# main_board.net
KiCad netlist of a schematic drawn in EAGLE
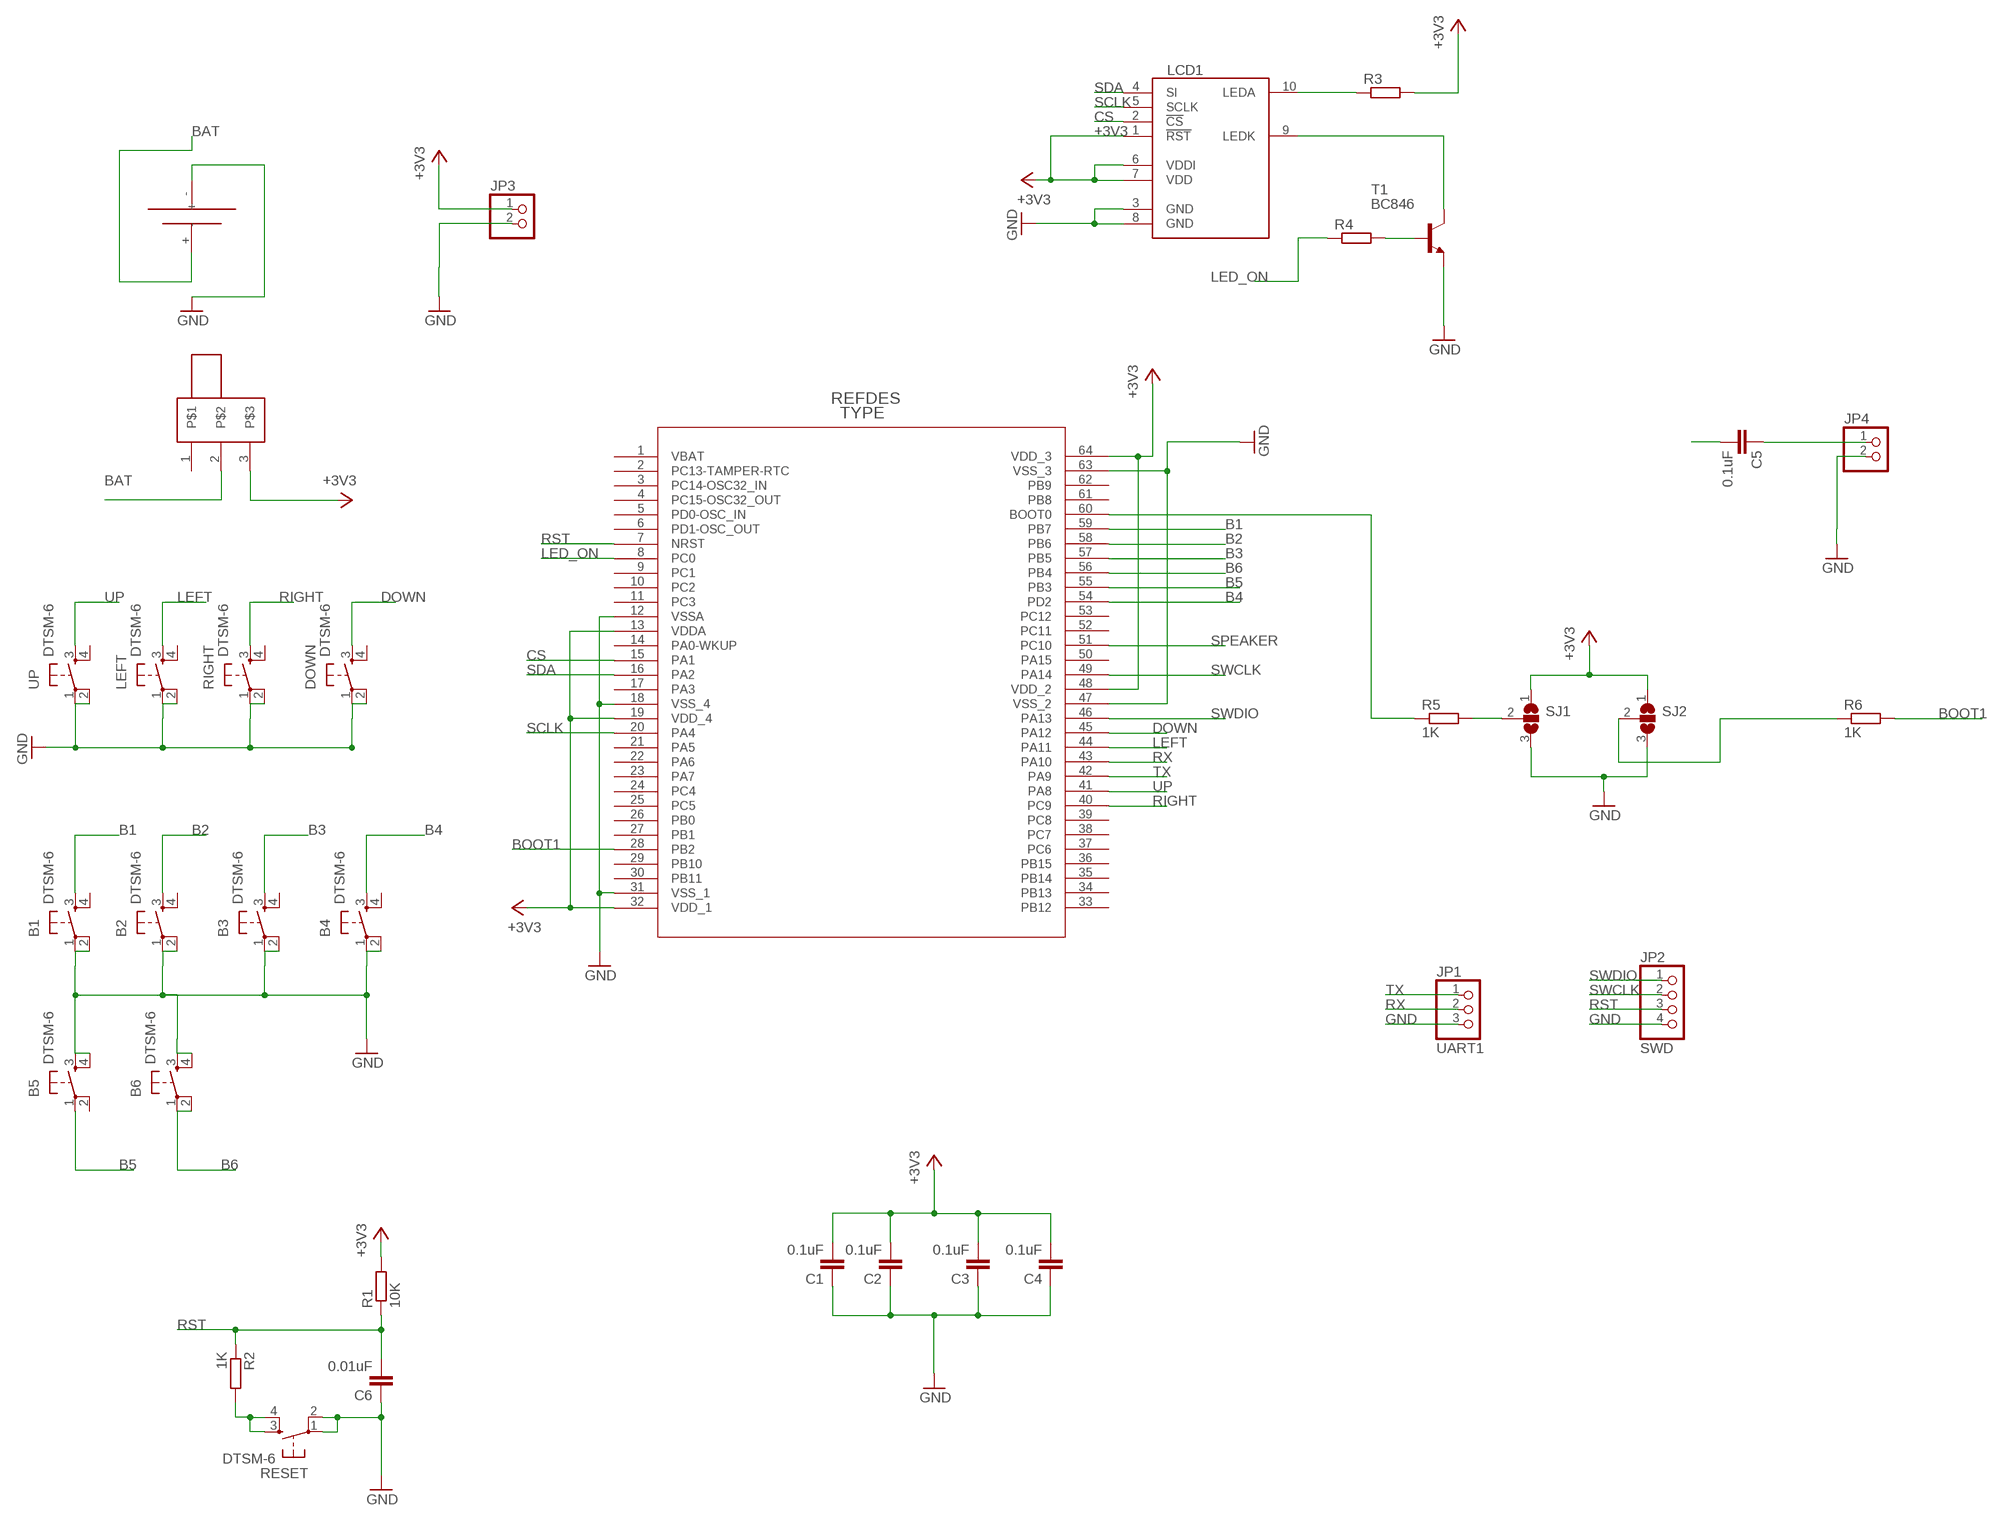
[diagram p0: schematic, sheet 1]

(export (version "E")
  (design (tool "Eeschema 10.0.6"))
  (components
    (comp (ref "B1")
      (value "DTSM-6")
      (footprint "eagle-import:DTSM-6")
      (libsource (lib "eagle-import") (part "DTSM-6"))
    )
    (comp (ref "B2")
      (value "DTSM-6")
      (footprint "eagle-import:DTSM-6")
      (libsource (lib "eagle-import") (part "DTSM-6"))
    )
    (comp (ref "B3")
      (value "DTSM-6")
      (footprint "eagle-import:DTSM-6")
      (libsource (lib "eagle-import") (part "DTSM-6"))
    )
    (comp (ref "B4")
      (value "DTSM-6")
      (footprint "eagle-import:DTSM-6")
      (libsource (lib "eagle-import") (part "DTSM-6"))
    )
    (comp (ref "B5")
      (value "DTSM-6")
      (footprint "eagle-import:DTSM-6")
      (libsource (lib "eagle-import") (part "DTSM-6"))
    )
    (comp (ref "B6")
      (value "DTSM-6")
      (footprint "eagle-import:DTSM-6")
      (libsource (lib "eagle-import") (part "DTSM-6"))
    )
    (comp (ref "C1")
      (value "0.1uF")
      (footprint "eagle-import:C1206")
      (libsource (lib "eagle-import") (part "C-EUC1206"))
    )
    (comp (ref "C2")
      (value "0.1uF")
      (footprint "eagle-import:C1206")
      (libsource (lib "eagle-import") (part "C-EUC1206"))
    )
    (comp (ref "C3")
      (value "0.1uF")
      (footprint "eagle-import:C1206")
      (libsource (lib "eagle-import") (part "C-EUC1206"))
    )
    (comp (ref "C4")
      (value "0.1uF")
      (footprint "eagle-import:C1206")
      (libsource (lib "eagle-import") (part "C-EUC1206"))
    )
    (comp (ref "C5")
      (value "0.1uF")
      (footprint "eagle-import:C1206")
      (libsource (lib "eagle-import") (part "C-EUC1206"))
    )
    (comp (ref "C6")
      (value "0.01uF")
      (footprint "eagle-import:C1206")
      (libsource (lib "eagle-import") (part "C-EUC1206"))
    )
    (comp (ref "DOWN")
      (value "DTSM-6")
      (footprint "eagle-import:DTSM-6")
      (libsource (lib "eagle-import") (part "DTSM-6"))
    )
    (comp (ref "JP1")
      (value "UART1")
      (footprint "eagle-import:1X03_90")
      (libsource (lib "eagle-import") (part "PINHD-1X3/90"))
    )
    (comp (ref "JP2")
      (value "SWD")
      (footprint "eagle-import:1X04_90")
      (libsource (lib "eagle-import") (part "PINHD-1X4/90"))
    )
    (comp (ref "JP3")
      (value "PINHD-1X2")
      (footprint "eagle-import:1X02")
      (libsource (lib "eagle-import") (part "PINHD-1X2"))
    )
    (comp (ref "JP4")
      (value "PINHD-1X2")
      (footprint "eagle-import:1X02")
      (libsource (lib "eagle-import") (part "PINHD-1X2"))
    )
    (comp (ref "LCD1")
      (value "LCD1202")
      (footprint "eagle-import:NOKIA1202LCD")
      (libsource (lib "eagle-import") (part "LCD1202"))
    )
    (comp (ref "LEFT")
      (value "DTSM-6")
      (footprint "eagle-import:DTSM-6")
      (libsource (lib "eagle-import") (part "DTSM-6"))
    )
    (comp (ref "R1")
      (value "10K")
      (footprint "eagle-import:R1206")
      (libsource (lib "eagle-import") (part "R-EU_R1206"))
    )
    (comp (ref "R2")
      (value "1K")
      (footprint "eagle-import:R1206")
      (libsource (lib "eagle-import") (part "R-EU_R1206"))
    )
    (comp (ref "R3")
      (value "R-EU_R1206")
      (footprint "eagle-import:R1206")
      (libsource (lib "eagle-import") (part "R-EU_R1206"))
    )
    (comp (ref "R4")
      (value "R-EU_R1206")
      (footprint "eagle-import:R1206")
      (libsource (lib "eagle-import") (part "R-EU_R1206"))
    )
    (comp (ref "R5")
      (value "1K")
      (footprint "eagle-import:R1206")
      (libsource (lib "eagle-import") (part "R-EU_R1206"))
    )
    (comp (ref "R6")
      (value "1K")
      (footprint "eagle-import:R1206")
      (libsource (lib "eagle-import") (part "R-EU_R1206"))
    )
    (comp (ref "RESET")
      (value "DTSM-6")
      (footprint "eagle-import:DTSM-6")
      (libsource (lib "eagle-import") (part "DTSM-6"))
    )
    (comp (ref "RIGHT")
      (value "DTSM-6")
      (footprint "eagle-import:DTSM-6")
      (libsource (lib "eagle-import") (part "DTSM-6"))
    )
    (comp (ref "SJ1")
      (value "SJ2W")
      (footprint "eagle-import:SJ_2")
      (libsource (lib "eagle-import") (part "SJ2W"))
    )
    (comp (ref "SJ2")
      (value "SJ2W")
      (footprint "eagle-import:SJ_2")
      (libsource (lib "eagle-import") (part "SJ2W"))
    )
    (comp (ref "T1")
      (value "BC846")
      (footprint "eagle-import:SOT23")
      (libsource (lib "eagle-import") (part "BC846"))
    )
    (comp (ref "U$1")
      (value "STM32F100RBT6B")
      (footprint "eagle-import:LQFP-64")
      (libsource (lib "eagle-import") (part "STM32F100RBT6B"))
    )
    (comp (ref "U$2")
      (value "BAT33")
      (footprint "eagle-import:3V3BATPACK")
      (libsource (lib "eagle-import") (part "BAT33"))
    )
    (comp (ref "U$3")
      (value "SWITCH3")
      (footprint "eagle-import:SWITCH3")
      (libsource (lib "eagle-import") (part "SWITCH3"))
    )
    (comp (ref "UP")
      (value "DTSM-6")
      (footprint "eagle-import:DTSM-6")
      (libsource (lib "eagle-import") (part "DTSM-6"))
    )
  )
  (nets
    (net (code "1") (name "+3V3") (class "Default")
      (node (ref "C1") (pin "2") (pinfunction "2_2") (pintype "passive"))
      (node (ref "C2") (pin "2") (pinfunction "2_2") (pintype "passive"))
      (node (ref "C3") (pin "2") (pinfunction "2_2") (pintype "passive"))
      (node (ref "C4") (pin "2") (pinfunction "2_2") (pintype "passive"))
      (node (ref "JP3") (pin "1") (pinfunction "1_1") (pintype "passive"))
      (node (ref "LCD1") (pin "1") (pinfunction "~{RST}_1") (pintype "input"))
      (node (ref "LCD1") (pin "6") (pinfunction "VDDI_6") (pintype "power_in"))
      (node (ref "LCD1") (pin "7") (pinfunction "VDD_7") (pintype "power_in"))
      (node (ref "R1") (pin "2") (pinfunction "2_2") (pintype "passive"))
      (node (ref "R3") (pin "2") (pinfunction "2_2") (pintype "passive"))
      (node (ref "SJ1") (pin "1") (pinfunction "1_1") (pintype "passive"))
      (node (ref "SJ2") (pin "1") (pinfunction "1_1") (pintype "passive"))
      (node (ref "U$1") (pin "13") (pinfunction "VDDA_13") (pintype "passive"))
      (node (ref "U$1") (pin "19") (pinfunction "VDD_4_19") (pintype "passive"))
      (node (ref "U$1") (pin "32") (pinfunction "VDD_1_32") (pintype "passive"))
      (node (ref "U$1") (pin "48") (pinfunction "VDD_2_48") (pintype "passive"))
      (node (ref "U$1") (pin "64") (pinfunction "VDD_3_64") (pintype "passive"))
      (node (ref "U$3") (pin "3") (pinfunction "P$3_3") (pintype "bidirectional"))
    )
    (net (code "2") (name "/B1") (class "Default")
      (node (ref "B1") (pin "3") (pinfunction "3_3") (pintype "passive"))
      (node (ref "U$1") (pin "59") (pinfunction "PB7_59") (pintype "passive"))
    )
    (net (code "3") (name "/B2") (class "Default")
      (node (ref "B2") (pin "3") (pinfunction "3_3") (pintype "passive"))
      (node (ref "U$1") (pin "58") (pinfunction "PB6_58") (pintype "passive"))
    )
    (net (code "4") (name "/B3") (class "Default")
      (node (ref "B3") (pin "3") (pinfunction "3_3") (pintype "passive"))
      (node (ref "U$1") (pin "57") (pinfunction "PB5_57") (pintype "passive"))
    )
    (net (code "5") (name "/B4") (class "Default")
      (node (ref "B4") (pin "3") (pinfunction "3_3") (pintype "passive"))
      (node (ref "U$1") (pin "54") (pinfunction "PD2_54") (pintype "passive"))
    )
    (net (code "6") (name "/B5") (class "Default")
      (node (ref "B5") (pin "1") (pinfunction "1_1") (pintype "passive"))
      (node (ref "U$1") (pin "55") (pinfunction "PB3_55") (pintype "passive"))
    )
    (net (code "7") (name "/B6") (class "Default")
      (node (ref "B6") (pin "1") (pinfunction "1_1") (pintype "passive"))
      (node (ref "B6") (pin "2") (pinfunction "2_2") (pintype "passive"))
      (node (ref "U$1") (pin "56") (pinfunction "PB4_56") (pintype "passive"))
    )
    (net (code "8") (name "/BAT") (class "Default")
      (node (ref "U$2") (pin "+") (pinfunction "+_+") (pintype "passive"))
      (node (ref "U$3") (pin "2") (pinfunction "P$2_2") (pintype "bidirectional"))
    )
    (net (code "9") (name "/BOOT1") (class "Default")
      (node (ref "R6") (pin "2") (pinfunction "2_2") (pintype "passive"))
      (node (ref "U$1") (pin "28") (pinfunction "PB2_28") (pintype "passive"))
    )
    (net (code "10") (name "/CS") (class "Default")
      (node (ref "LCD1") (pin "2") (pinfunction "~{CS}_2") (pintype "input"))
      (node (ref "U$1") (pin "15") (pinfunction "PA1_15") (pintype "passive"))
    )
    (net (code "11") (name "/DOWN") (class "Default")
      (node (ref "DOWN") (pin "3") (pinfunction "3_3") (pintype "passive"))
      (node (ref "U$1") (pin "45") (pinfunction "PA12_45") (pintype "passive"))
    )
    (net (code "12") (name "/LED_ON") (class "Default")
      (node (ref "R4") (pin "1") (pinfunction "1_1") (pintype "passive"))
      (node (ref "U$1") (pin "8") (pinfunction "PC0_8") (pintype "passive"))
    )
    (net (code "13") (name "/LEFT") (class "Default")
      (node (ref "LEFT") (pin "3") (pinfunction "3_3") (pintype "passive"))
      (node (ref "U$1") (pin "44") (pinfunction "PA11_44") (pintype "passive"))
    )
    (net (code "14") (name "/RIGHT") (class "Default")
      (node (ref "RIGHT") (pin "3") (pinfunction "3_3") (pintype "passive"))
      (node (ref "U$1") (pin "40") (pinfunction "PC9_40") (pintype "passive"))
    )
    (net (code "15") (name "/RST") (class "Default")
      (node (ref "C6") (pin "2") (pinfunction "2_2") (pintype "passive"))
      (node (ref "JP2") (pin "3") (pinfunction "3_3") (pintype "passive"))
      (node (ref "R1") (pin "1") (pinfunction "1_1") (pintype "passive"))
      (node (ref "R2") (pin "1") (pinfunction "1_1") (pintype "passive"))
      (node (ref "U$1") (pin "7") (pinfunction "NRST_7") (pintype "passive"))
    )
    (net (code "16") (name "/RX") (class "Default")
      (node (ref "JP1") (pin "2") (pinfunction "2_2") (pintype "passive"))
      (node (ref "U$1") (pin "43") (pinfunction "PA10_43") (pintype "passive"))
    )
    (net (code "17") (name "/SCLK") (class "Default")
      (node (ref "LCD1") (pin "5") (pinfunction "SCLK_5") (pintype "input"))
      (node (ref "U$1") (pin "20") (pinfunction "PA4_20") (pintype "passive"))
    )
    (net (code "18") (name "/SDA") (class "Default")
      (node (ref "LCD1") (pin "4") (pinfunction "SI_4") (pintype "input"))
      (node (ref "U$1") (pin "16") (pinfunction "PA2_16") (pintype "passive"))
    )
    (net (code "19") (name "/SPEAKER") (class "Default")
      (node (ref "C5") (pin "2") (pinfunction "2_2") (pintype "passive"))
      (node (ref "U$1") (pin "51") (pinfunction "PC10_51") (pintype "passive"))
    )
    (net (code "20") (name "/SWCLK") (class "Default")
      (node (ref "JP2") (pin "2") (pinfunction "2_2") (pintype "passive"))
      (node (ref "U$1") (pin "49") (pinfunction "PA14_49") (pintype "passive"))
    )
    (net (code "21") (name "/SWDIO") (class "Default")
      (node (ref "JP2") (pin "1") (pinfunction "1_1") (pintype "passive"))
      (node (ref "U$1") (pin "46") (pinfunction "PA13_46") (pintype "passive"))
    )
    (net (code "22") (name "/TX") (class "Default")
      (node (ref "JP1") (pin "1") (pinfunction "1_1") (pintype "passive"))
      (node (ref "U$1") (pin "42") (pinfunction "PA9_42") (pintype "passive"))
    )
    (net (code "23") (name "/UP") (class "Default")
      (node (ref "U$1") (pin "41") (pinfunction "PA8_41") (pintype "passive"))
      (node (ref "UP") (pin "3") (pinfunction "3_3") (pintype "passive"))
    )
    (net (code "24") (name "GND") (class "Default")
      (node (ref "B1") (pin "1") (pinfunction "1_1") (pintype "passive"))
      (node (ref "B1") (pin "2") (pinfunction "2_2") (pintype "passive"))
      (node (ref "B2") (pin "1") (pinfunction "1_1") (pintype "passive"))
      (node (ref "B2") (pin "2") (pinfunction "2_2") (pintype "passive"))
      (node (ref "B3") (pin "1") (pinfunction "1_1") (pintype "passive"))
      (node (ref "B3") (pin "2") (pinfunction "2_2") (pintype "passive"))
      (node (ref "B4") (pin "1") (pinfunction "1_1") (pintype "passive"))
      (node (ref "B4") (pin "2") (pinfunction "2_2") (pintype "passive"))
      (node (ref "B5") (pin "3") (pinfunction "3_3") (pintype "passive"))
      (node (ref "B5") (pin "4") (pinfunction "4_4") (pintype "passive"))
      (node (ref "B6") (pin "3") (pinfunction "3_3") (pintype "passive"))
      (node (ref "B6") (pin "4") (pinfunction "4_4") (pintype "passive"))
      (node (ref "C1") (pin "1") (pinfunction "1_1") (pintype "passive"))
      (node (ref "C2") (pin "1") (pinfunction "1_1") (pintype "passive"))
      (node (ref "C3") (pin "1") (pinfunction "1_1") (pintype "passive"))
      (node (ref "C4") (pin "1") (pinfunction "1_1") (pintype "passive"))
      (node (ref "C6") (pin "1") (pinfunction "1_1") (pintype "passive"))
      (node (ref "DOWN") (pin "1") (pinfunction "1_1") (pintype "passive"))
      (node (ref "DOWN") (pin "2") (pinfunction "2_2") (pintype "passive"))
      (node (ref "JP1") (pin "3") (pinfunction "3_3") (pintype "passive"))
      (node (ref "JP2") (pin "4") (pinfunction "4_4") (pintype "passive"))
      (node (ref "JP3") (pin "2") (pinfunction "2_2") (pintype "passive"))
      (node (ref "JP4") (pin "2") (pinfunction "2_2") (pintype "passive"))
      (node (ref "LCD1") (pin "3") (pinfunction "GND_3") (pintype "power_in"))
      (node (ref "LCD1") (pin "8") (pinfunction "GND_8") (pintype "power_in"))
      (node (ref "LEFT") (pin "1") (pinfunction "1_1") (pintype "passive"))
      (node (ref "LEFT") (pin "2") (pinfunction "2_2") (pintype "passive"))
      (node (ref "RESET") (pin "1") (pinfunction "1_1") (pintype "passive"))
      (node (ref "RESET") (pin "2") (pinfunction "2_2") (pintype "passive"))
      (node (ref "RIGHT") (pin "1") (pinfunction "1_1") (pintype "passive"))
      (node (ref "RIGHT") (pin "2") (pinfunction "2_2") (pintype "passive"))
      (node (ref "SJ1") (pin "3") (pinfunction "3_3") (pintype "passive"))
      (node (ref "SJ2") (pin "3") (pinfunction "3_3") (pintype "passive"))
      (node (ref "T1") (pin "2") (pinfunction "E_2") (pintype "passive"))
      (node (ref "U$1") (pin "12") (pinfunction "VSSA_12") (pintype "passive"))
      (node (ref "U$1") (pin "18") (pinfunction "VSS_4_18") (pintype "passive"))
      (node (ref "U$1") (pin "31") (pinfunction "VSS_1_31") (pintype "passive"))
      (node (ref "U$1") (pin "47") (pinfunction "VSS_2_47") (pintype "passive"))
      (node (ref "U$1") (pin "63") (pinfunction "VSS_3_63") (pintype "passive"))
      (node (ref "U$2") (pin "-") (pinfunction "-_-") (pintype "passive"))
      (node (ref "UP") (pin "1") (pinfunction "1_1") (pintype "passive"))
      (node (ref "UP") (pin "2") (pinfunction "2_2") (pintype "passive"))
    )
    (net (code "25") (name "Net-(C5-Pad1)") (class "Default")
      (node (ref "C5") (pin "1") (pinfunction "1_1") (pintype "passive"))
      (node (ref "JP4") (pin "1") (pinfunction "1_1") (pintype "passive"))
    )
    (net (code "26") (name "Net-(LCD1-LEDA)") (class "Default")
      (node (ref "LCD1") (pin "10") (pinfunction "LEDA_10") (pintype "passive"))
      (node (ref "R3") (pin "1") (pinfunction "1_1") (pintype "passive"))
    )
    (net (code "27") (name "Net-(LCD1-LEDK)") (class "Default")
      (node (ref "LCD1") (pin "9") (pinfunction "LEDK_9") (pintype "passive"))
      (node (ref "T1") (pin "3") (pinfunction "C_3") (pintype "passive"))
    )
    (net (code "28") (name "Net-(R2-Pad2)") (class "Default")
      (node (ref "R2") (pin "2") (pinfunction "2_2") (pintype "passive"))
      (node (ref "RESET") (pin "3") (pinfunction "3_3") (pintype "passive"))
      (node (ref "RESET") (pin "4") (pinfunction "4_4") (pintype "passive"))
    )
    (net (code "29") (name "Net-(R5-Pad2)") (class "Default")
      (node (ref "R5") (pin "2") (pinfunction "2_2") (pintype "passive"))
      (node (ref "SJ1") (pin "2") (pinfunction "2_2") (pintype "passive"))
    )
    (net (code "30") (name "Net-(R6-Pad1)") (class "Default")
      (node (ref "R6") (pin "1") (pinfunction "1_1") (pintype "passive"))
      (node (ref "SJ2") (pin "2") (pinfunction "2_2") (pintype "passive"))
    )
    (net (code "31") (name "Net-(T1-B)") (class "Default")
      (node (ref "R4") (pin "2") (pinfunction "2_2") (pintype "passive"))
      (node (ref "T1") (pin "1") (pinfunction "B_1") (pintype "passive"))
    )
    (net (code "32") (name "Net-(U$1-BOOT0)") (class "Default")
      (node (ref "R5") (pin "1") (pinfunction "1_1") (pintype "passive"))
      (node (ref "U$1") (pin "60") (pinfunction "BOOT0_60") (pintype "passive"))
    )
    (net (code "33") (name "unconnected-(B1-Pad4)") (class "Default")
      (node (ref "B1") (pin "4") (pinfunction "4_4") (pintype "passive"))
    )
    (net (code "34") (name "unconnected-(B2-Pad4)") (class "Default")
      (node (ref "B2") (pin "4") (pinfunction "4_4") (pintype "passive"))
    )
    (net (code "35") (name "unconnected-(B3-Pad4)") (class "Default")
      (node (ref "B3") (pin "4") (pinfunction "4_4") (pintype "passive"))
    )
    (net (code "36") (name "unconnected-(B4-Pad4)") (class "Default")
      (node (ref "B4") (pin "4") (pinfunction "4_4") (pintype "passive"))
    )
    (net (code "37") (name "unconnected-(B5-Pad2)") (class "Default")
      (node (ref "B5") (pin "2") (pinfunction "2_2") (pintype "passive"))
    )
    (net (code "38") (name "unconnected-(DOWN-Pad4)") (class "Default")
      (node (ref "DOWN") (pin "4") (pinfunction "4_4") (pintype "passive"))
    )
    (net (code "39") (name "unconnected-(LEFT-Pad4)") (class "Default")
      (node (ref "LEFT") (pin "4") (pinfunction "4_4") (pintype "passive"))
    )
    (net (code "40") (name "unconnected-(RIGHT-Pad4)") (class "Default")
      (node (ref "RIGHT") (pin "4") (pinfunction "4_4") (pintype "passive"))
    )
    (net (code "41") (name "unconnected-(U$1-PA0-WKUP-Pad14)") (class "Default")
      (node (ref "U$1") (pin "14") (pinfunction "PA0-WKUP_14") (pintype "passive"))
    )
    (net (code "42") (name "unconnected-(U$1-PA3-Pad17)") (class "Default")
      (node (ref "U$1") (pin "17") (pinfunction "PA3_17") (pintype "passive"))
    )
    (net (code "43") (name "unconnected-(U$1-PA5-Pad21)") (class "Default")
      (node (ref "U$1") (pin "21") (pinfunction "PA5_21") (pintype "passive"))
    )
    (net (code "44") (name "unconnected-(U$1-PA6-Pad22)") (class "Default")
      (node (ref "U$1") (pin "22") (pinfunction "PA6_22") (pintype "passive"))
    )
    (net (code "45") (name "unconnected-(U$1-PA7-Pad23)") (class "Default")
      (node (ref "U$1") (pin "23") (pinfunction "PA7_23") (pintype "passive"))
    )
    (net (code "46") (name "unconnected-(U$1-PA15-Pad50)") (class "Default")
      (node (ref "U$1") (pin "50") (pinfunction "PA15_50") (pintype "passive"))
    )
    (net (code "47") (name "unconnected-(U$1-PB0-Pad26)") (class "Default")
      (node (ref "U$1") (pin "26") (pinfunction "PB0_26") (pintype "passive"))
    )
    (net (code "48") (name "unconnected-(U$1-PB1-Pad27)") (class "Default")
      (node (ref "U$1") (pin "27") (pinfunction "PB1_27") (pintype "passive"))
    )
    (net (code "49") (name "unconnected-(U$1-PB8-Pad61)") (class "Default")
      (node (ref "U$1") (pin "61") (pinfunction "PB8_61") (pintype "passive"))
    )
    (net (code "50") (name "unconnected-(U$1-PB9-Pad62)") (class "Default")
      (node (ref "U$1") (pin "62") (pinfunction "PB9_62") (pintype "passive"))
    )
    (net (code "51") (name "unconnected-(U$1-PB10-Pad29)") (class "Default")
      (node (ref "U$1") (pin "29") (pinfunction "PB10_29") (pintype "passive"))
    )
    (net (code "52") (name "unconnected-(U$1-PB11-Pad30)") (class "Default")
      (node (ref "U$1") (pin "30") (pinfunction "PB11_30") (pintype "passive"))
    )
    (net (code "53") (name "unconnected-(U$1-PB12-Pad33)") (class "Default")
      (node (ref "U$1") (pin "33") (pinfunction "PB12_33") (pintype "passive"))
    )
    (net (code "54") (name "unconnected-(U$1-PB13-Pad34)") (class "Default")
      (node (ref "U$1") (pin "34") (pinfunction "PB13_34") (pintype "passive"))
    )
    (net (code "55") (name "unconnected-(U$1-PB14-Pad35)") (class "Default")
      (node (ref "U$1") (pin "35") (pinfunction "PB14_35") (pintype "passive"))
    )
    (net (code "56") (name "unconnected-(U$1-PB15-Pad36)") (class "Default")
      (node (ref "U$1") (pin "36") (pinfunction "PB15_36") (pintype "passive"))
    )
    (net (code "57") (name "unconnected-(U$1-PC1-Pad9)") (class "Default")
      (node (ref "U$1") (pin "9") (pinfunction "PC1_9") (pintype "passive"))
    )
    (net (code "58") (name "unconnected-(U$1-PC2-Pad10)") (class "Default")
      (node (ref "U$1") (pin "10") (pinfunction "PC2_10") (pintype "passive"))
    )
    (net (code "59") (name "unconnected-(U$1-PC3-Pad11)") (class "Default")
      (node (ref "U$1") (pin "11") (pinfunction "PC3_11") (pintype "passive"))
    )
    (net (code "60") (name "unconnected-(U$1-PC4-Pad24)") (class "Default")
      (node (ref "U$1") (pin "24") (pinfunction "PC4_24") (pintype "passive"))
    )
    (net (code "61") (name "unconnected-(U$1-PC5-Pad25)") (class "Default")
      (node (ref "U$1") (pin "25") (pinfunction "PC5_25") (pintype "passive"))
    )
    (net (code "62") (name "unconnected-(U$1-PC6-Pad37)") (class "Default")
      (node (ref "U$1") (pin "37") (pinfunction "PC6_37") (pintype "passive"))
    )
    (net (code "63") (name "unconnected-(U$1-PC7-Pad38)") (class "Default")
      (node (ref "U$1") (pin "38") (pinfunction "PC7_38") (pintype "passive"))
    )
    (net (code "64") (name "unconnected-(U$1-PC8-Pad39)") (class "Default")
      (node (ref "U$1") (pin "39") (pinfunction "PC8_39") (pintype "passive"))
    )
    (net (code "65") (name "unconnected-(U$1-PC11-Pad52)") (class "Default")
      (node (ref "U$1") (pin "52") (pinfunction "PC11_52") (pintype "passive"))
    )
    (net (code "66") (name "unconnected-(U$1-PC12-Pad53)") (class "Default")
      (node (ref "U$1") (pin "53") (pinfunction "PC12_53") (pintype "passive"))
    )
    (net (code "67") (name "unconnected-(U$1-PC13-TAMPER-RTC-Pad2)") (class "Default")
      (node (ref "U$1") (pin "2") (pinfunction "PC13-TAMPER-RTC_2") (pintype "passive"))
    )
    (net (code "68") (name "unconnected-(U$1-PC14-OSC32_IN-Pad3)") (class "Default")
      (node (ref "U$1") (pin "3") (pinfunction "PC14-OSC32_IN_3") (pintype "passive"))
    )
    (net (code "69") (name "unconnected-(U$1-PC15-OSC32_OUT-Pad4)") (class "Default")
      (node (ref "U$1") (pin "4") (pinfunction "PC15-OSC32_OUT_4") (pintype "passive"))
    )
    (net (code "70") (name "unconnected-(U$1-PD0-OSC_IN-Pad5)") (class "Default")
      (node (ref "U$1") (pin "5") (pinfunction "PD0-OSC_IN_5") (pintype "passive"))
    )
    (net (code "71") (name "unconnected-(U$1-PD1-OSC_OUT-Pad6)") (class "Default")
      (node (ref "U$1") (pin "6") (pinfunction "PD1-OSC_OUT_6") (pintype "passive"))
    )
    (net (code "72") (name "unconnected-(U$1-VBAT-Pad1)") (class "Default")
      (node (ref "U$1") (pin "1") (pinfunction "VBAT_1") (pintype "passive"))
    )
    (net (code "73") (name "unconnected-(U$3-P$1-Pad1)") (class "Default")
      (node (ref "U$3") (pin "1") (pinfunction "P$1_1") (pintype "bidirectional"))
    )
    (net (code "74") (name "unconnected-(UP-Pad4)") (class "Default")
      (node (ref "UP") (pin "4") (pinfunction "4_4") (pintype "passive"))
    )
  )
)
